# Controller.net
KiCad netlist of a schematic drawn in Altium Designer
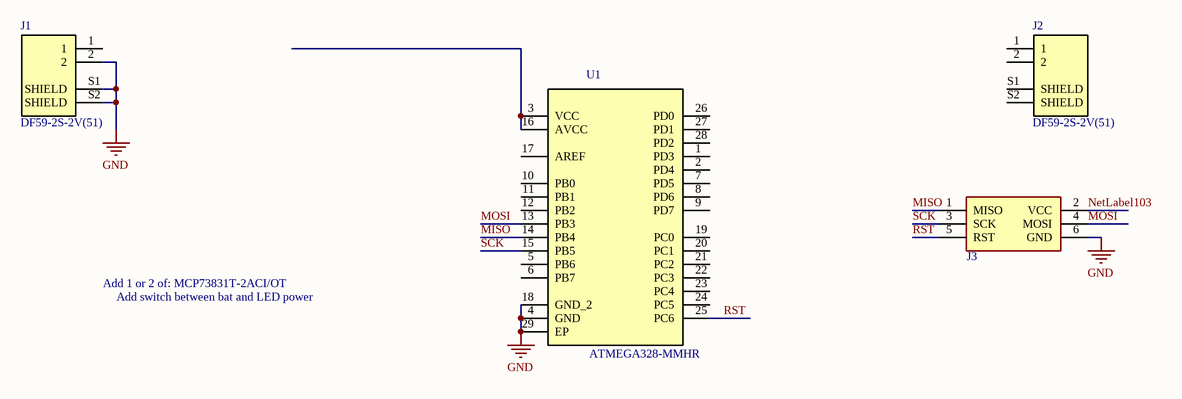
[diagram p0: Controller.SchDoc]

(export (version "E")
  (design (tool "Eeschema 10.0.6"))
  (components
    (comp (ref "J1")
      (value "DF59-2S-2V(51)")
      (footprint "SNAPBEE_DF59-2S-2V")
      (description "CONN SSL RCPT 2POS 2MM SOLDER")
      (libsource (lib "Connectors") (part "SNAPBEE_DF59-2S-2V"))
    )
    (comp (ref "J2")
      (value "DF59-2S-2V(51)")
      (footprint "SNAPBEE_DF59-2S-2V")
      (description "CONN SSL RCPT 2POS 2MM SOLDER")
      (libsource (lib "") (part "SNAPBEE_DF59-2S-2V_1"))
    )
    (comp (ref "J3")
      (value "6 Pin ISP Header")
      (footprint "CONN_ISP_M")
      (libsource (lib "Connectors") (part "ISP"))
    )
    (comp (ref "U1")
      (value "ATMEGA328-MMHR")
      (footprint "Common Components:QFN-28_4x4")
      (description "IC MCU 8BIT 32KB FLASH 28VQFN")
      (fields (field (name "MF") "Microchip") (field (name "MP") "ATMEGA328P-PU"))
      (libsource (lib "Microcontrollers") (part "ATMEGA328-MMHR"))
    )
  )
  (nets
    (net (code "1") (name "/MISO") (class "Default")
      (node (ref "J3") (pin "1") (pinfunction "MISO_1") (pintype "passive"))
      (node (ref "U1") (pin "14") (pinfunction "PB4_14") (pintype "passive"))
    )
    (net (code "2") (name "/MOSI") (class "Default")
      (node (ref "J3") (pin "4") (pinfunction "MOSI_4") (pintype "passive"))
      (node (ref "U1") (pin "13") (pinfunction "PB3_13") (pintype "passive"))
    )
    (net (code "3") (name "/NetLabel103") (class "Default")
      (node (ref "J3") (pin "2") (pinfunction "VCC_2") (pintype "passive"))
    )
    (net (code "4") (name "/RST") (class "Default")
      (node (ref "J3") (pin "5") (pinfunction "RST_5") (pintype "passive"))
      (node (ref "U1") (pin "25") (pinfunction "PC6_25") (pintype "passive"))
    )
    (net (code "5") (name "/SCK") (class "Default")
      (node (ref "J3") (pin "3") (pinfunction "SCK_3") (pintype "passive"))
      (node (ref "U1") (pin "15") (pinfunction "PB5_15") (pintype "passive"))
    )
    (net (code "6") (name "GND") (class "Default")
      (node (ref "J1") (pin "2") (pinfunction "2_2") (pintype "passive"))
      (node (ref "J1") (pin "S1") (pinfunction "SHIELD_S1") (pintype "passive"))
      (node (ref "J1") (pin "S2") (pinfunction "SHIELD_S2") (pintype "passive"))
      (node (ref "J3") (pin "6") (pinfunction "GND_6") (pintype "passive"))
      (node (ref "U1") (pin "18") (pinfunction "GND_2_18") (pintype "passive"))
      (node (ref "U1") (pin "29") (pinfunction "EP_29") (pintype "passive"))
      (node (ref "U1") (pin "4") (pinfunction "GND_4") (pintype "passive"))
    )
    (net (code "7") (name "Net-(U1-AVCC)") (class "Default")
      (node (ref "U1") (pin "16") (pinfunction "AVCC_16") (pintype "power_in"))
      (node (ref "U1") (pin "3") (pinfunction "VCC_3") (pintype "power_in"))
    )
    (net (code "8") (name "unconnected-(J1-Pad1)") (class "Default")
      (node (ref "J1") (pin "1") (pinfunction "1_1") (pintype "power_in"))
    )
    (net (code "9") (name "unconnected-(J2-Pad1)") (class "Default")
      (node (ref "J2") (pin "1") (pinfunction "1_1") (pintype "power_in"))
    )
    (net (code "10") (name "unconnected-(J2-Pad2)") (class "Default")
      (node (ref "J2") (pin "2") (pinfunction "2_2") (pintype "passive"))
    )
    (net (code "11") (name "unconnected-(J2-SHIELD-PadS1)") (class "Default")
      (node (ref "J2") (pin "S1") (pinfunction "SHIELD_S1") (pintype "passive"))
    )
    (net (code "12") (name "unconnected-(J2-SHIELD-PadS2)") (class "Default")
      (node (ref "J2") (pin "S2") (pinfunction "SHIELD_S2") (pintype "passive"))
    )
    (net (code "13") (name "unconnected-(U1-AREF-Pad17)") (class "Default")
      (node (ref "U1") (pin "17") (pinfunction "AREF_17") (pintype "passive"))
    )
    (net (code "14") (name "unconnected-(U1-PB0-Pad10)") (class "Default")
      (node (ref "U1") (pin "10") (pinfunction "PB0_10") (pintype "passive"))
    )
    (net (code "15") (name "unconnected-(U1-PB1-Pad11)") (class "Default")
      (node (ref "U1") (pin "11") (pinfunction "PB1_11") (pintype "passive"))
    )
    (net (code "16") (name "unconnected-(U1-PB2-Pad12)") (class "Default")
      (node (ref "U1") (pin "12") (pinfunction "PB2_12") (pintype "passive"))
    )
    (net (code "17") (name "unconnected-(U1-PB6-Pad5)") (class "Default")
      (node (ref "U1") (pin "5") (pinfunction "PB6_5") (pintype "passive"))
    )
    (net (code "18") (name "unconnected-(U1-PB7-Pad6)") (class "Default")
      (node (ref "U1") (pin "6") (pinfunction "PB7_6") (pintype "passive"))
    )
    (net (code "19") (name "unconnected-(U1-PC0-Pad19)") (class "Default")
      (node (ref "U1") (pin "19") (pinfunction "PC0_19") (pintype "passive"))
    )
    (net (code "20") (name "unconnected-(U1-PC1-Pad20)") (class "Default")
      (node (ref "U1") (pin "20") (pinfunction "PC1_20") (pintype "passive"))
    )
    (net (code "21") (name "unconnected-(U1-PC2-Pad21)") (class "Default")
      (node (ref "U1") (pin "21") (pinfunction "PC2_21") (pintype "passive"))
    )
    (net (code "22") (name "unconnected-(U1-PC3-Pad22)") (class "Default")
      (node (ref "U1") (pin "22") (pinfunction "PC3_22") (pintype "passive"))
    )
    (net (code "23") (name "unconnected-(U1-PC4-Pad23)") (class "Default")
      (node (ref "U1") (pin "23") (pinfunction "PC4_23") (pintype "passive"))
    )
    (net (code "24") (name "unconnected-(U1-PC5-Pad24)") (class "Default")
      (node (ref "U1") (pin "24") (pinfunction "PC5_24") (pintype "passive"))
    )
    (net (code "25") (name "unconnected-(U1-PD0-Pad26)") (class "Default")
      (node (ref "U1") (pin "26") (pinfunction "PD0_26") (pintype "passive"))
    )
    (net (code "26") (name "unconnected-(U1-PD1-Pad27)") (class "Default")
      (node (ref "U1") (pin "27") (pinfunction "PD1_27") (pintype "passive"))
    )
    (net (code "27") (name "unconnected-(U1-PD2-Pad28)") (class "Default")
      (node (ref "U1") (pin "28") (pinfunction "PD2_28") (pintype "passive"))
    )
    (net (code "28") (name "unconnected-(U1-PD3-Pad1)") (class "Default")
      (node (ref "U1") (pin "1") (pinfunction "PD3_1") (pintype "passive"))
    )
    (net (code "29") (name "unconnected-(U1-PD4-Pad2)") (class "Default")
      (node (ref "U1") (pin "2") (pinfunction "PD4_2") (pintype "passive"))
    )
    (net (code "30") (name "unconnected-(U1-PD5-Pad7)") (class "Default")
      (node (ref "U1") (pin "7") (pinfunction "PD5_7") (pintype "passive"))
    )
    (net (code "31") (name "unconnected-(U1-PD6-Pad8)") (class "Default")
      (node (ref "U1") (pin "8") (pinfunction "PD6_8") (pintype "passive"))
    )
    (net (code "32") (name "unconnected-(U1-PD7-Pad9)") (class "Default")
      (node (ref "U1") (pin "9") (pinfunction "PD7_9") (pintype "passive"))
    )
  )
)
